# 09-UART.net
KiCad netlist of a schematic drawn in Altium Designer
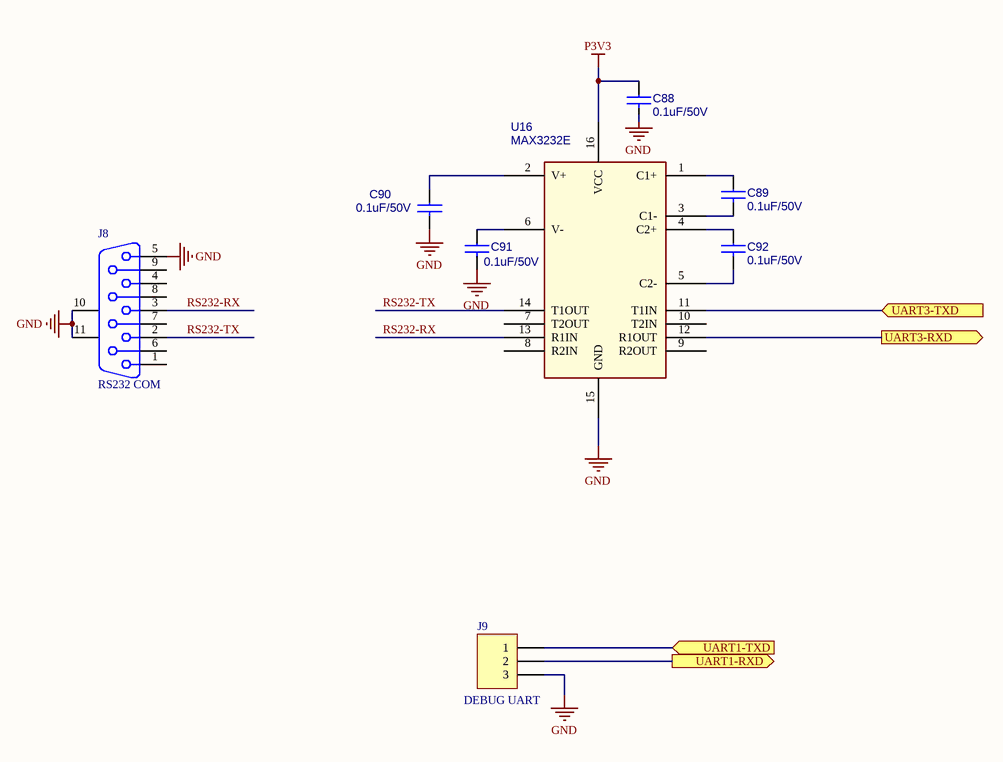
[diagram p0: 09-UART.SchDoc]

(export (version "E")
  (design (tool "Eeschema 10.0.6"))
  (components
    (comp (ref "C88") (value "0.1uF/50V") (libsource (lib "*") (part "CAP")))
    (comp (ref "C89") (value "0.1uF/50V") (libsource (lib "*") (part "CAP")))
    (comp (ref "C90") (value "0.1uF/50V") (libsource (lib "*") (part "CAP")))
    (comp (ref "C91") (value "0.1uF/50V") (libsource (lib "*") (part "CAP")))
    (comp (ref "C92") (value "0.1uF/50V") (libsource (lib "*") (part "CAP")))
    (comp (ref "J8")
      (value "RS232 COM")
      (footprint "DB9-F")
      (description "Receptacle Assembly, 9 Position, Right Angle")
      (fields (field (name "PUBLISHER") "Altium Limited"))
      (libsource (lib "Miscellaneous Connectors") (part "D Connector 9"))
    )
    (comp (ref "J9")
      (value "DEBUG UART")
      (footprint "HDR1X3")
      (description "Header, 3-Pin")
      (fields (field (name "PUBLISHER") "Altium Limited"))
      (libsource (lib "Miscellaneous Connectors") (part "Header 3"))
    )
    (comp (ref "U16") (value "MAX3232E") (footprint "SO-16") (libsource (lib "*") (part "MAX3232")))
  )
  (nets
    (net (code "1") (name "/RS232-RX") (class "Default")
      (node (ref "J8") (pin "3") (pinfunction "3_3") (pintype "passive"))
      (node (ref "U16") (pin "13") (pinfunction "R1IN_13") (pintype "passive"))
    )
    (net (code "2") (name "/RS232-TX") (class "Default")
      (node (ref "J8") (pin "2") (pinfunction "2_2") (pintype "passive"))
      (node (ref "U16") (pin "14") (pinfunction "T1OUT_14") (pintype "passive"))
    )
    (net (code "3") (name "/UART1-RXD") (class "Default")
      (node (ref "J9") (pin "2") (pinfunction "2_2") (pintype "passive"))
    )
    (net (code "4") (name "/UART1-TXD") (class "Default")
      (node (ref "J9") (pin "1") (pinfunction "1_1") (pintype "passive"))
    )
    (net (code "5") (name "/UART3-RXD") (class "Default")
      (node (ref "U16") (pin "12") (pinfunction "R1OUT_12") (pintype "passive"))
    )
    (net (code "6") (name "/UART3-TXD") (class "Default")
      (node (ref "U16") (pin "11") (pinfunction "T1IN_11") (pintype "passive"))
    )
    (net (code "7") (name "GND") (class "Default")
      (node (ref "C88") (pin "2") (pinfunction "2_2") (pintype "passive"))
      (node (ref "C90") (pin "2") (pinfunction "2_2") (pintype "passive"))
      (node (ref "C91") (pin "2") (pinfunction "2_2") (pintype "passive"))
      (node (ref "J8") (pin "10") (pinfunction "MH1_10") (pintype "passive"))
      (node (ref "J8") (pin "11") (pinfunction "MH2_11") (pintype "passive"))
      (node (ref "J8") (pin "5") (pinfunction "5_5") (pintype "passive"))
      (node (ref "J9") (pin "3") (pinfunction "3_3") (pintype "passive"))
      (node (ref "U16") (pin "15") (pinfunction "GND_15") (pintype "passive"))
    )
    (net (code "8") (name "Net-(U16-C1+)") (class "Default")
      (node (ref "C89") (pin "1") (pinfunction "1_1") (pintype "passive"))
      (node (ref "U16") (pin "1") (pinfunction "C1+_1") (pintype "passive"))
    )
    (net (code "9") (name "Net-(U16-C1-)") (class "Default")
      (node (ref "C89") (pin "2") (pinfunction "2_2") (pintype "passive"))
      (node (ref "U16") (pin "3") (pinfunction "C1-_3") (pintype "passive"))
    )
    (net (code "10") (name "Net-(U16-C2+)") (class "Default")
      (node (ref "C92") (pin "1") (pinfunction "1_1") (pintype "passive"))
      (node (ref "U16") (pin "4") (pinfunction "C2+_4") (pintype "passive"))
    )
    (net (code "11") (name "Net-(U16-C2-)") (class "Default")
      (node (ref "C92") (pin "2") (pinfunction "2_2") (pintype "passive"))
      (node (ref "U16") (pin "5") (pinfunction "C2-_5") (pintype "passive"))
    )
    (net (code "12") (name "Net-(U16-V+)") (class "Default")
      (node (ref "C90") (pin "1") (pinfunction "1_1") (pintype "passive"))
      (node (ref "U16") (pin "2") (pinfunction "V+_2") (pintype "passive"))
    )
    (net (code "13") (name "Net-(U16-V-)") (class "Default")
      (node (ref "C91") (pin "1") (pinfunction "1_1") (pintype "passive"))
      (node (ref "U16") (pin "6") (pinfunction "V-_6") (pintype "passive"))
    )
    (net (code "14") (name "P3V3") (class "Default")
      (node (ref "C88") (pin "1") (pinfunction "1_1") (pintype "passive"))
      (node (ref "U16") (pin "16") (pinfunction "VCC_16") (pintype "passive"))
    )
    (net (code "15") (name "unconnected-(J8-Pad1)") (class "Default")
      (node (ref "J8") (pin "1") (pinfunction "1_1") (pintype "passive"))
    )
    (net (code "16") (name "unconnected-(J8-Pad4)") (class "Default")
      (node (ref "J8") (pin "4") (pinfunction "4_4") (pintype "passive"))
    )
    (net (code "17") (name "unconnected-(J8-Pad6)") (class "Default")
      (node (ref "J8") (pin "6") (pinfunction "6_6") (pintype "passive"))
    )
    (net (code "18") (name "unconnected-(J8-Pad7)") (class "Default")
      (node (ref "J8") (pin "7") (pinfunction "7_7") (pintype "passive"))
    )
    (net (code "19") (name "unconnected-(J8-Pad8)") (class "Default")
      (node (ref "J8") (pin "8") (pinfunction "8_8") (pintype "passive"))
    )
    (net (code "20") (name "unconnected-(J8-Pad9)") (class "Default")
      (node (ref "J8") (pin "9") (pinfunction "9_9") (pintype "passive"))
    )
    (net (code "21") (name "unconnected-(U16-R2IN-Pad8)") (class "Default")
      (node (ref "U16") (pin "8") (pinfunction "R2IN_8") (pintype "passive"))
    )
    (net (code "22") (name "unconnected-(U16-R2OUT-Pad9)") (class "Default")
      (node (ref "U16") (pin "9") (pinfunction "R2OUT_9") (pintype "passive"))
    )
    (net (code "23") (name "unconnected-(U16-T2IN-Pad10)") (class "Default")
      (node (ref "U16") (pin "10") (pinfunction "T2IN_10") (pintype "passive"))
    )
    (net (code "24") (name "unconnected-(U16-T2OUT-Pad7)") (class "Default")
      (node (ref "U16") (pin "7") (pinfunction "T2OUT_7") (pintype "passive"))
    )
  )
)
